# 4_ch_sample-and-hold_without_mux_v1_1.net
KiCad netlist of a schematic drawn in EAGLE
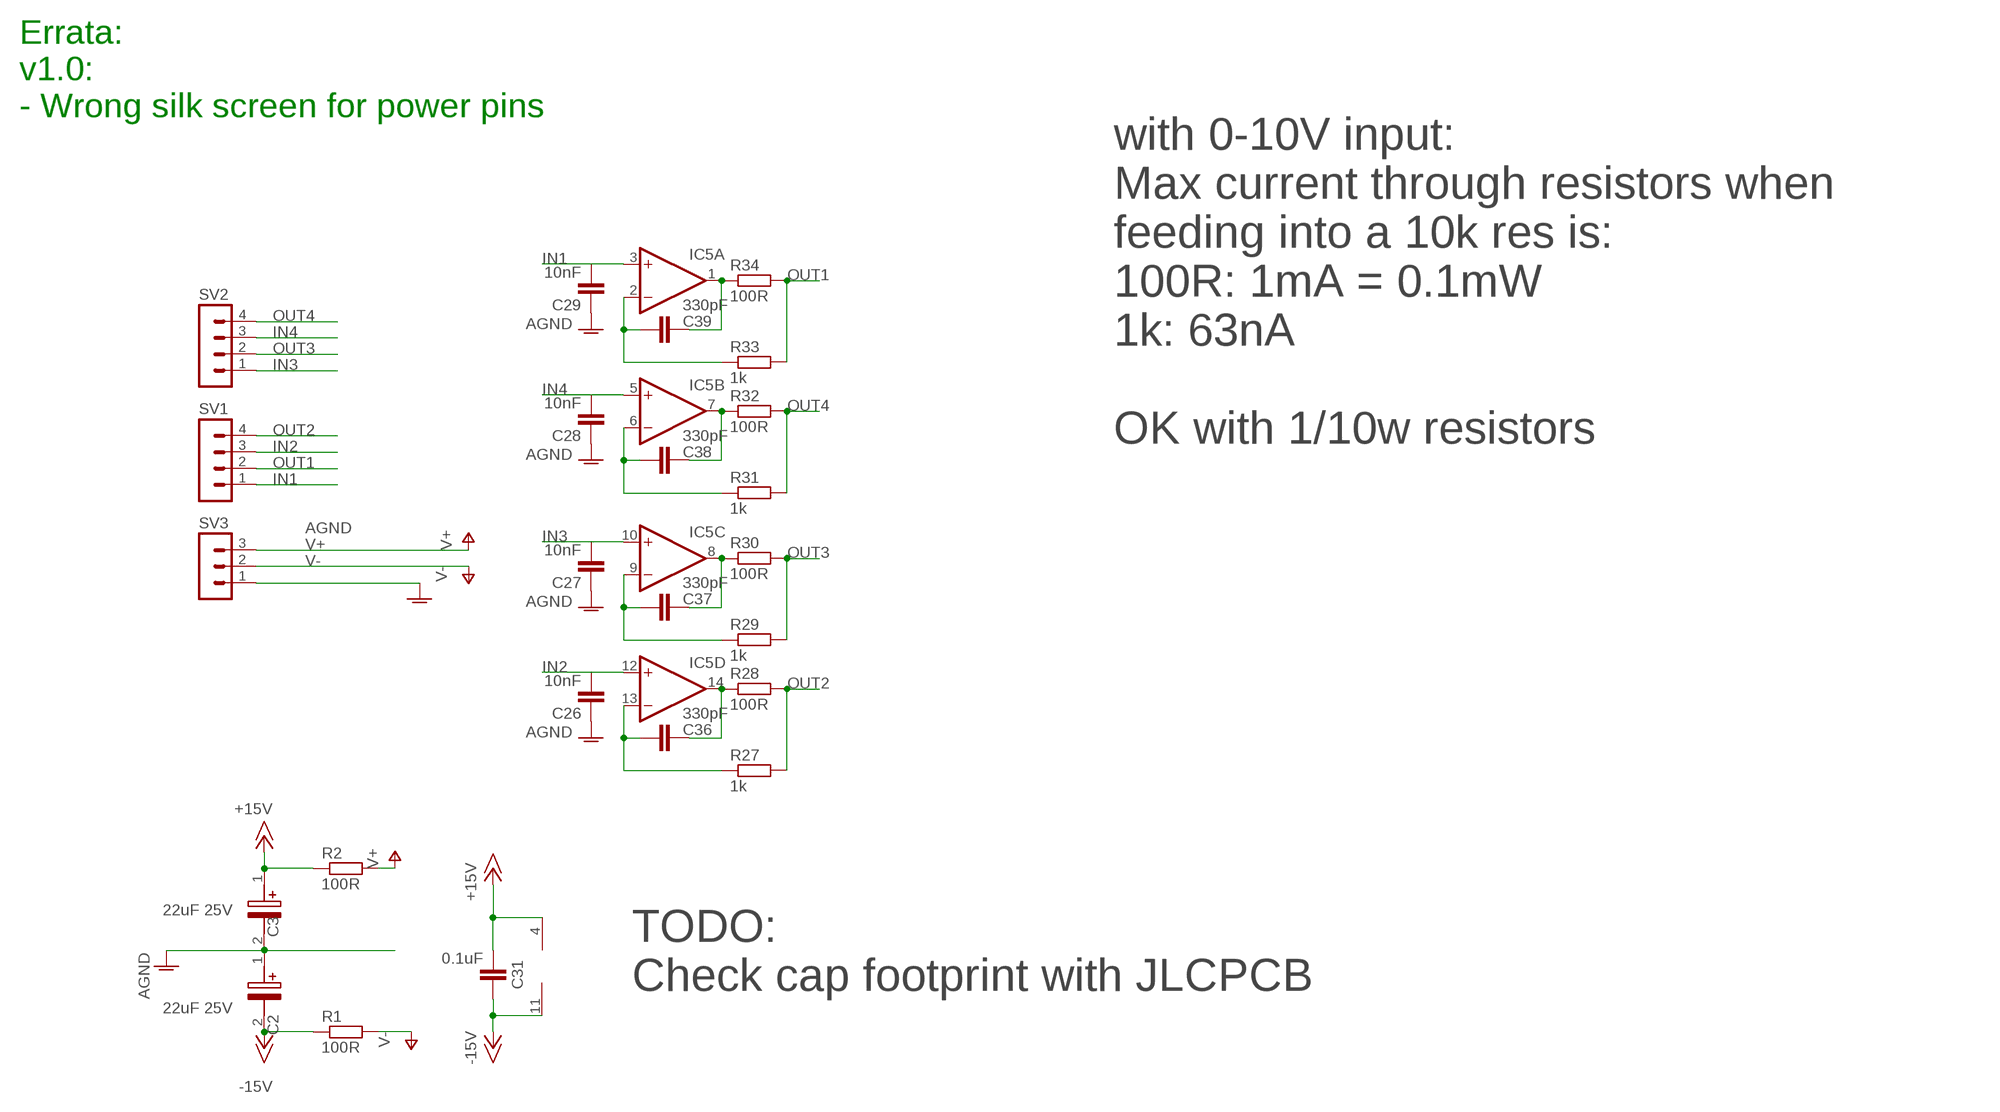
[diagram p0: schematic, sheet 1]

(export (version "E")
  (design (tool "Eeschema 10.0.6"))
  (components
    (comp (ref "C2")
      (value "22uF 25V")
      (footprint "eagle-import:CAPAE660X610N")
      (fields
        (field (name "MANUFACTURER_PART_NUMBER") "VZL101M1CTR-0606")
        (field (name "MOUSER_PART_NUMBER") "140-VZL101M1CTR-0606")
      )
      (libsource (lib "eagle-import") (part "VZL101M1CTR-0606"))
    )
    (comp (ref "C3")
      (value "22uF 25V")
      (footprint "eagle-import:CAPAE660X610N")
      (fields
        (field (name "MANUFACTURER_PART_NUMBER") "VZL101M1CTR-0606")
        (field (name "MOUSER_PART_NUMBER") "140-VZL101M1CTR-0606")
      )
      (libsource (lib "eagle-import") (part "VZL101M1CTR-0606"))
    )
    (comp (ref "C26")
      (value "10nF")
      (footprint "eagle-import:C0805")
      (libsource (lib "eagle-import") (part "C-EUC0805"))
    )
    (comp (ref "C27")
      (value "10nF")
      (footprint "eagle-import:C0805")
      (libsource (lib "eagle-import") (part "C-EUC0805"))
    )
    (comp (ref "C28")
      (value "10nF")
      (footprint "eagle-import:C0805")
      (libsource (lib "eagle-import") (part "C-EUC0805"))
    )
    (comp (ref "C29")
      (value "10nF")
      (footprint "eagle-import:C0805")
      (libsource (lib "eagle-import") (part "C-EUC0805"))
    )
    (comp (ref "C31")
      (value "0.1uF")
      (footprint "eagle-import:C0603")
      (libsource (lib "eagle-import") (part "resistor_C-EUC0603"))
    )
    (comp (ref "C36")
      (value "330pF")
      (footprint "eagle-import:C0603")
      (libsource (lib "eagle-import") (part "resistor_C-EUC0603"))
    )
    (comp (ref "C37")
      (value "330pF")
      (footprint "eagle-import:C0603")
      (libsource (lib "eagle-import") (part "resistor_C-EUC0603"))
    )
    (comp (ref "C38")
      (value "330pF")
      (footprint "eagle-import:C0603")
      (libsource (lib "eagle-import") (part "resistor_C-EUC0603"))
    )
    (comp (ref "C39")
      (value "330pF")
      (footprint "eagle-import:C0603")
      (libsource (lib "eagle-import") (part "resistor_C-EUC0603"))
    )
    (comp (ref "IC5")
      (value "TL074D")
      (footprint "eagle-import:SO14")
      (libsource (lib "eagle-import") (part "TL074D"))
    )
    (comp (ref "R1")
      (value "100R")
      (footprint "eagle-import:R0805")
      (libsource (lib "eagle-import") (part "R-EU_R0805"))
    )
    (comp (ref "R2")
      (value "100R")
      (footprint "eagle-import:R0805")
      (libsource (lib "eagle-import") (part "R-EU_R0805"))
    )
    (comp (ref "R27")
      (value "1k")
      (footprint "eagle-import:R0603")
      (libsource (lib "eagle-import") (part "resistor_R-EU_R0603"))
    )
    (comp (ref "R28")
      (value "100R")
      (footprint "eagle-import:R0603")
      (libsource (lib "eagle-import") (part "resistor_R-EU_R0603"))
    )
    (comp (ref "R29")
      (value "1k")
      (footprint "eagle-import:R0603")
      (libsource (lib "eagle-import") (part "resistor_R-EU_R0603"))
    )
    (comp (ref "R30")
      (value "100R")
      (footprint "eagle-import:R0603")
      (libsource (lib "eagle-import") (part "resistor_R-EU_R0603"))
    )
    (comp (ref "R31")
      (value "1k")
      (footprint "eagle-import:R0603")
      (libsource (lib "eagle-import") (part "resistor_R-EU_R0603"))
    )
    (comp (ref "R32")
      (value "100R")
      (footprint "eagle-import:R0603")
      (libsource (lib "eagle-import") (part "resistor_R-EU_R0603"))
    )
    (comp (ref "R33")
      (value "1k")
      (footprint "eagle-import:R0603")
      (libsource (lib "eagle-import") (part "resistor_R-EU_R0603"))
    )
    (comp (ref "R34")
      (value "100R")
      (footprint "eagle-import:R0603")
      (libsource (lib "eagle-import") (part "resistor_R-EU_R0603"))
    )
    (comp (ref "SV1")
      (value "MA04-1JP")
      (footprint "eagle-import:SIP-PIN04-1J")
      (libsource (lib "eagle-import") (part "MA04-1JP"))
    )
    (comp (ref "SV2")
      (value "MA04-1JP")
      (footprint "eagle-import:SIP-PIN04-1J")
      (libsource (lib "eagle-import") (part "MA04-1JP"))
    )
    (comp (ref "SV3")
      (value "MA03-1JP")
      (footprint "eagle-import:SIP-PIN03-1J")
      (libsource (lib "eagle-import") (part "MA03-1JP"))
    )
  )
  (nets
    (net (code "1") (name "+15V") (class "Default")
      (node (ref "C3") (pin "1") (pinfunction "+_1") (pintype "bidirectional"))
      (node (ref "C31") (pin "1") (pinfunction "1_1") (pintype "passive"))
      (node (ref "IC5") (pin "4") (pinfunction "V+_4") (pintype "power_in"))
      (node (ref "R2") (pin "1") (pinfunction "1_1") (pintype "passive"))
    )
    (net (code "2") (name "-15V") (class "Default")
      (node (ref "C2") (pin "2") (pinfunction "-_2") (pintype "bidirectional"))
      (node (ref "C31") (pin "2") (pinfunction "2_2") (pintype "passive"))
      (node (ref "IC5") (pin "11") (pinfunction "V-_11") (pintype "power_in"))
      (node (ref "R1") (pin "1") (pinfunction "1_1") (pintype "passive"))
    )
    (net (code "3") (name "/IN1") (class "Default")
      (node (ref "C29") (pin "2") (pinfunction "2_2") (pintype "passive"))
      (node (ref "IC5") (pin "3") (pinfunction "+IN_3") (pintype "input"))
      (node (ref "SV1") (pin "1") (pinfunction "1_1") (pintype "passive"))
    )
    (net (code "4") (name "/IN2") (class "Default")
      (node (ref "C26") (pin "2") (pinfunction "2_2") (pintype "passive"))
      (node (ref "IC5") (pin "12") (pinfunction "+IN_12") (pintype "input"))
      (node (ref "SV1") (pin "3") (pinfunction "3_3") (pintype "passive"))
    )
    (net (code "5") (name "/IN3") (class "Default")
      (node (ref "C27") (pin "2") (pinfunction "2_2") (pintype "passive"))
      (node (ref "IC5") (pin "10") (pinfunction "+IN_10") (pintype "input"))
      (node (ref "SV2") (pin "1") (pinfunction "1_1") (pintype "passive"))
    )
    (net (code "6") (name "/IN4") (class "Default")
      (node (ref "C28") (pin "2") (pinfunction "2_2") (pintype "passive"))
      (node (ref "IC5") (pin "5") (pinfunction "+IN_5") (pintype "input"))
      (node (ref "SV2") (pin "3") (pinfunction "3_3") (pintype "passive"))
    )
    (net (code "7") (name "/OUT1") (class "Default")
      (node (ref "R33") (pin "2") (pinfunction "2_2") (pintype "passive"))
      (node (ref "R34") (pin "2") (pinfunction "2_2") (pintype "passive"))
      (node (ref "SV1") (pin "2") (pinfunction "2_2") (pintype "passive"))
    )
    (net (code "8") (name "/OUT2") (class "Default")
      (node (ref "R27") (pin "2") (pinfunction "2_2") (pintype "passive"))
      (node (ref "R28") (pin "2") (pinfunction "2_2") (pintype "passive"))
      (node (ref "SV1") (pin "4") (pinfunction "4_4") (pintype "passive"))
    )
    (net (code "9") (name "/OUT3") (class "Default")
      (node (ref "R29") (pin "2") (pinfunction "2_2") (pintype "passive"))
      (node (ref "R30") (pin "2") (pinfunction "2_2") (pintype "passive"))
      (node (ref "SV2") (pin "2") (pinfunction "2_2") (pintype "passive"))
    )
    (net (code "10") (name "/OUT4") (class "Default")
      (node (ref "R31") (pin "2") (pinfunction "2_2") (pintype "passive"))
      (node (ref "R32") (pin "2") (pinfunction "2_2") (pintype "passive"))
      (node (ref "SV2") (pin "4") (pinfunction "4_4") (pintype "passive"))
    )
    (net (code "11") (name "AGND") (class "Default")
      (node (ref "C2") (pin "1") (pinfunction "+_1") (pintype "bidirectional"))
      (node (ref "C26") (pin "1") (pinfunction "1_1") (pintype "passive"))
      (node (ref "C27") (pin "1") (pinfunction "1_1") (pintype "passive"))
      (node (ref "C28") (pin "1") (pinfunction "1_1") (pintype "passive"))
      (node (ref "C29") (pin "1") (pinfunction "1_1") (pintype "passive"))
      (node (ref "C3") (pin "2") (pinfunction "-_2") (pintype "bidirectional"))
      (node (ref "SV3") (pin "1") (pinfunction "1_1") (pintype "passive"))
    )
    (net (code "12") (name "Net-(IC5A--IN)") (class "Default")
      (node (ref "C39") (pin "2") (pinfunction "2_2") (pintype "passive"))
      (node (ref "IC5") (pin "2") (pinfunction "-IN_2") (pintype "input"))
      (node (ref "R33") (pin "1") (pinfunction "1_1") (pintype "passive"))
    )
    (net (code "13") (name "Net-(IC5A-OUT)") (class "Default")
      (node (ref "C39") (pin "1") (pinfunction "1_1") (pintype "passive"))
      (node (ref "IC5") (pin "1") (pinfunction "OUT_1") (pintype "output"))
      (node (ref "R34") (pin "1") (pinfunction "1_1") (pintype "passive"))
    )
    (net (code "14") (name "Net-(IC5B--IN)") (class "Default")
      (node (ref "C38") (pin "2") (pinfunction "2_2") (pintype "passive"))
      (node (ref "IC5") (pin "6") (pinfunction "-IN_6") (pintype "input"))
      (node (ref "R31") (pin "1") (pinfunction "1_1") (pintype "passive"))
    )
    (net (code "15") (name "Net-(IC5B-OUT)") (class "Default")
      (node (ref "C38") (pin "1") (pinfunction "1_1") (pintype "passive"))
      (node (ref "IC5") (pin "7") (pinfunction "OUT_7") (pintype "output"))
      (node (ref "R32") (pin "1") (pinfunction "1_1") (pintype "passive"))
    )
    (net (code "16") (name "Net-(IC5C--IN)") (class "Default")
      (node (ref "C37") (pin "2") (pinfunction "2_2") (pintype "passive"))
      (node (ref "IC5") (pin "9") (pinfunction "-IN_9") (pintype "input"))
      (node (ref "R29") (pin "1") (pinfunction "1_1") (pintype "passive"))
    )
    (net (code "17") (name "Net-(IC5C-OUT)") (class "Default")
      (node (ref "C37") (pin "1") (pinfunction "1_1") (pintype "passive"))
      (node (ref "IC5") (pin "8") (pinfunction "OUT_8") (pintype "output"))
      (node (ref "R30") (pin "1") (pinfunction "1_1") (pintype "passive"))
    )
    (net (code "18") (name "Net-(IC5D--IN)") (class "Default")
      (node (ref "C36") (pin "2") (pinfunction "2_2") (pintype "passive"))
      (node (ref "IC5") (pin "13") (pinfunction "-IN_13") (pintype "input"))
      (node (ref "R27") (pin "1") (pinfunction "1_1") (pintype "passive"))
    )
    (net (code "19") (name "Net-(IC5D-OUT)") (class "Default")
      (node (ref "C36") (pin "1") (pinfunction "1_1") (pintype "passive"))
      (node (ref "IC5") (pin "14") (pinfunction "OUT_14") (pintype "output"))
      (node (ref "R28") (pin "1") (pinfunction "1_1") (pintype "passive"))
    )
    (net (code "20") (name "V+") (class "Default")
      (node (ref "R2") (pin "2") (pinfunction "2_2") (pintype "passive"))
      (node (ref "SV3") (pin "3") (pinfunction "3_3") (pintype "passive"))
    )
    (net (code "21") (name "V-") (class "Default")
      (node (ref "R1") (pin "2") (pinfunction "2_2") (pintype "passive"))
      (node (ref "SV3") (pin "2") (pinfunction "2_2") (pintype "passive"))
    )
  )
)
